# skmagiik_thing.net
KiCad netlist of a schematic drawn in EAGLE
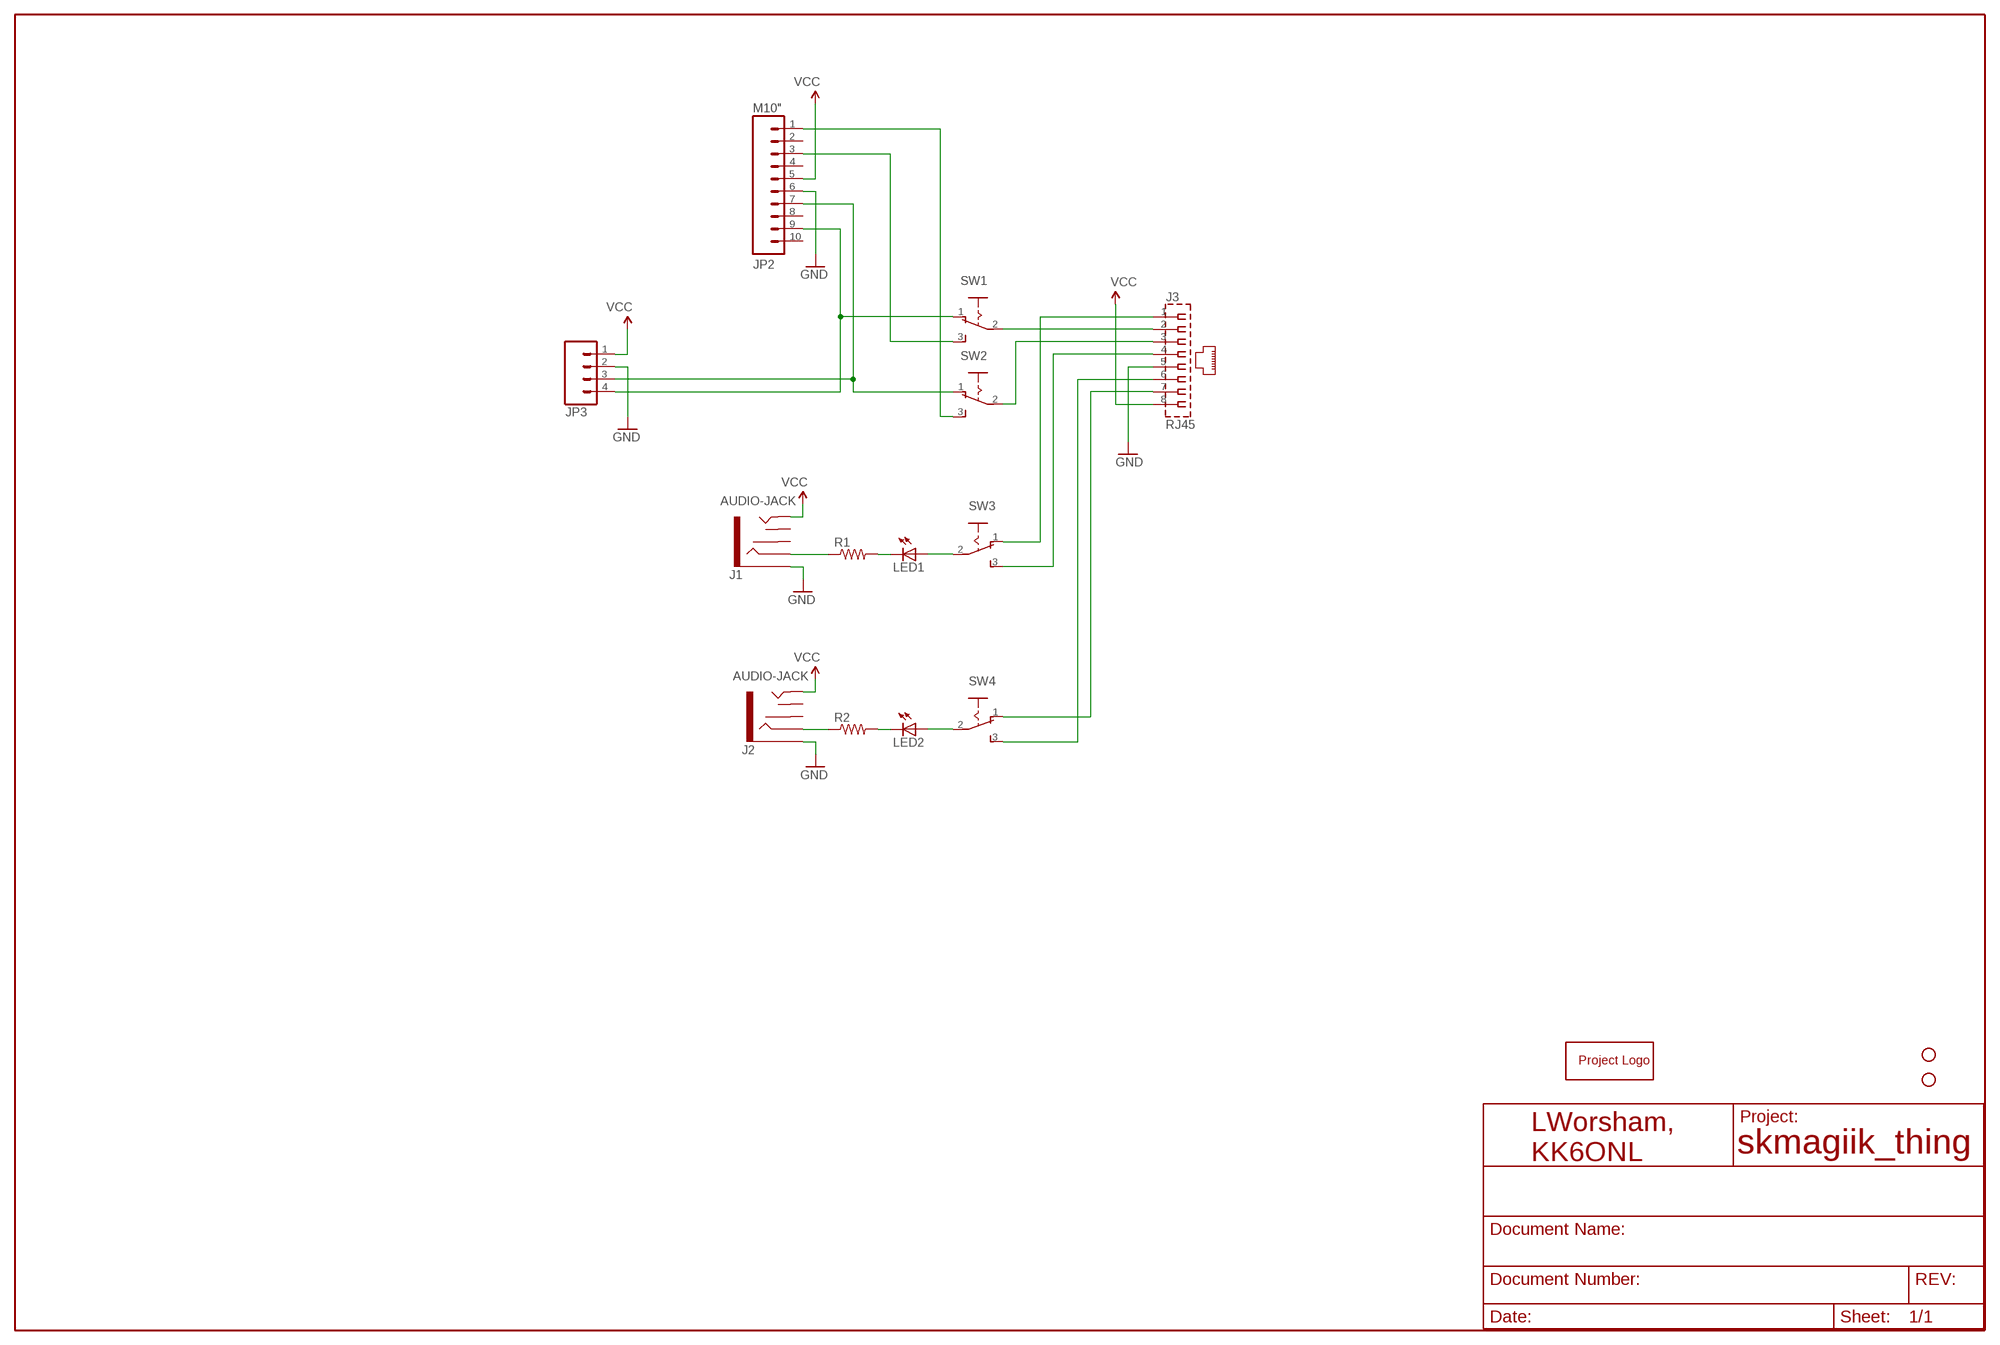
[diagram p0: schematic, sheet 1]

(export (version "E")
  (design (tool "Eeschema 10.0.6"))
  (components
    (comp (ref "J1")
      (value "AUDIO-JACK")
      (footprint "eagle-import:AUDIO-JACK")
      (libsource (lib "eagle-import") (part "AUDIO-JACK2PTH"))
    )
    (comp (ref "J2")
      (value "AUDIO-JACK")
      (footprint "eagle-import:AUDIO-JACK")
      (libsource (lib "eagle-import") (part "AUDIO-JACK2PTH"))
    )
    (comp (ref "J3")
      (value "RJ45")
      (footprint "eagle-import:RJ45")
      (libsource (lib "eagle-import") (part "RJ45"))
    )
    (comp (ref "JP2")
      (value "M10\"")
      (footprint "eagle-import:1X10")
      (fields (field (name "NO_PART") "1"))
      (libsource (lib "eagle-import") (part "M10{dblquote}"))
    )
    (comp (ref "JP3")
      (value "M04PTH")
      (footprint "eagle-import:1X04")
      (libsource (lib "eagle-import") (part "M04PTH"))
    )
    (comp (ref "LED1")
      (value "LED3MM")
      (footprint "eagle-import:LED3MM")
      (libsource (lib "eagle-import") (part "LED3MM"))
    )
    (comp (ref "LED2")
      (value "LED3MM")
      (footprint "eagle-import:LED3MM")
      (libsource (lib "eagle-import") (part "LED3MM"))
    )
    (comp (ref "R1")
      (value "R-US_0207/10")
      (footprint "eagle-import:0207_10")
      (libsource (lib "eagle-import") (part "R-US_0207/10"))
    )
    (comp (ref "R2")
      (value "R-US_0207/10")
      (footprint "eagle-import:0207_10")
      (libsource (lib "eagle-import") (part "R-US_0207/10"))
    )
    (comp (ref "STANDOFF3")
      (value "STAND-OFF")
      (footprint "eagle-import:STAND-OFF")
      (libsource (lib "eagle-import") (part "STAND-OFF"))
    )
    (comp (ref "STANDOFF5")
      (value "STAND-OFF")
      (footprint "eagle-import:STAND-OFF")
      (libsource (lib "eagle-import") (part "STAND-OFF"))
    )
    (comp (ref "SW1")
      (value "M251")
      (footprint "eagle-import:M251")
      (libsource (lib "eagle-import") (part "M251"))
    )
    (comp (ref "SW2")
      (value "M251")
      (footprint "eagle-import:M251")
      (libsource (lib "eagle-import") (part "M251"))
    )
    (comp (ref "SW3")
      (value "M251")
      (footprint "eagle-import:M251")
      (libsource (lib "eagle-import") (part "M251"))
    )
    (comp (ref "SW4")
      (value "M251")
      (footprint "eagle-import:M251")
      (libsource (lib "eagle-import") (part "M251"))
    )
    (comp (ref "U$2")
      (value "PROJECT_LOGO")
      (footprint "eagle-import:BMP_TEST")
      (libsource (lib "eagle-import") (part "PROJECT_LOGO"))
    )
  )
  (nets
    (net (code "1") (name "GND") (class "Default")
      (node (ref "J1") (pin "SLEEVE") (pinfunction "SLEEVE_SLEEVE") (pintype "bidirectional"))
      (node (ref "J2") (pin "SLEEVE") (pinfunction "SLEEVE_SLEEVE") (pintype "bidirectional"))
      (node (ref "J3") (pin "5") (pinfunction "5_5") (pintype "passive"))
      (node (ref "JP2") (pin "6") (pinfunction "6_6") (pintype "passive"))
      (node (ref "JP3") (pin "2") (pinfunction "2_2") (pintype "passive"))
    )
    (net (code "2") (name "Net-(J1-PadRING)") (class "Default")
      (node (ref "J1") (pin "RING") (pinfunction "RING_RING") (pintype "bidirectional"))
      (node (ref "R1") (pin "1") (pinfunction "1_1") (pintype "passive"))
    )
    (net (code "3") (name "Net-(J2-PadRING)") (class "Default")
      (node (ref "J2") (pin "RING") (pinfunction "RING_RING") (pintype "bidirectional"))
      (node (ref "R2") (pin "1") (pinfunction "1_1") (pintype "passive"))
    )
    (net (code "4") (name "Net-(LED1-C)") (class "Default")
      (node (ref "LED1") (pin "K") (pinfunction "C_K") (pintype "passive"))
      (node (ref "R1") (pin "2") (pinfunction "2_2") (pintype "passive"))
    )
    (net (code "5") (name "Net-(LED2-C)") (class "Default")
      (node (ref "LED2") (pin "K") (pinfunction "C_K") (pintype "passive"))
      (node (ref "R2") (pin "2") (pinfunction "2_2") (pintype "passive"))
    )
    (net (code "6") (name "Net-(SW1-O)") (class "Default")
      (node (ref "JP2") (pin "9") (pinfunction "9_9") (pintype "passive"))
      (node (ref "JP3") (pin "4") (pinfunction "4_4") (pintype "passive"))
      (node (ref "SW1") (pin "1") (pinfunction "O_1") (pintype "passive"))
    )
    (net (code "7") (name "Net-(SW1-P)") (class "Default")
      (node (ref "J3") (pin "2") (pinfunction "2_2") (pintype "passive"))
      (node (ref "SW1") (pin "2") (pinfunction "P_2") (pintype "passive"))
    )
    (net (code "8") (name "Net-(SW1-S)") (class "Default")
      (node (ref "JP2") (pin "3") (pinfunction "3_3") (pintype "passive"))
      (node (ref "SW1") (pin "3") (pinfunction "S_3") (pintype "passive"))
    )
    (net (code "9") (name "Net-(SW2-O)") (class "Default")
      (node (ref "JP2") (pin "7") (pinfunction "7_7") (pintype "passive"))
      (node (ref "JP3") (pin "3") (pinfunction "3_3") (pintype "passive"))
      (node (ref "SW2") (pin "1") (pinfunction "O_1") (pintype "passive"))
    )
    (net (code "10") (name "Net-(SW2-P)") (class "Default")
      (node (ref "J3") (pin "3") (pinfunction "3_3") (pintype "passive"))
      (node (ref "SW2") (pin "2") (pinfunction "P_2") (pintype "passive"))
    )
    (net (code "11") (name "Net-(SW2-S)") (class "Default")
      (node (ref "JP2") (pin "1") (pinfunction "1_1") (pintype "passive"))
      (node (ref "SW2") (pin "3") (pinfunction "S_3") (pintype "passive"))
    )
    (net (code "12") (name "Net-(SW3-O)") (class "Default")
      (node (ref "J3") (pin "1") (pinfunction "1_1") (pintype "passive"))
      (node (ref "SW3") (pin "1") (pinfunction "O_1") (pintype "passive"))
    )
    (net (code "13") (name "Net-(SW3-P)") (class "Default")
      (node (ref "LED1") (pin "A") (pinfunction "A_A") (pintype "passive"))
      (node (ref "SW3") (pin "2") (pinfunction "P_2") (pintype "passive"))
    )
    (net (code "14") (name "Net-(SW3-S)") (class "Default")
      (node (ref "J3") (pin "4") (pinfunction "4_4") (pintype "passive"))
      (node (ref "SW3") (pin "3") (pinfunction "S_3") (pintype "passive"))
    )
    (net (code "15") (name "Net-(SW4-O)") (class "Default")
      (node (ref "J3") (pin "7") (pinfunction "7_7") (pintype "passive"))
      (node (ref "SW4") (pin "1") (pinfunction "O_1") (pintype "passive"))
    )
    (net (code "16") (name "Net-(SW4-P)") (class "Default")
      (node (ref "LED2") (pin "A") (pinfunction "A_A") (pintype "passive"))
      (node (ref "SW4") (pin "2") (pinfunction "P_2") (pintype "passive"))
    )
    (net (code "17") (name "Net-(SW4-S)") (class "Default")
      (node (ref "J3") (pin "6") (pinfunction "6_6") (pintype "passive"))
      (node (ref "SW4") (pin "3") (pinfunction "S_3") (pintype "passive"))
    )
    (net (code "18") (name "VCC") (class "Default")
      (node (ref "J1") (pin "TIP") (pinfunction "TIP_TIP") (pintype "bidirectional"))
      (node (ref "J2") (pin "TIP") (pinfunction "TIP_TIP") (pintype "bidirectional"))
      (node (ref "J3") (pin "8") (pinfunction "8_8") (pintype "passive"))
      (node (ref "JP2") (pin "5") (pinfunction "5_5") (pintype "passive"))
      (node (ref "JP3") (pin "1") (pinfunction "1_1") (pintype "passive"))
    )
    (net (code "19") (name "unconnected-(J1-PadRSH)") (class "Default")
      (node (ref "J1") (pin "RSH") (pinfunction "RSH_RSH") (pintype "bidirectional"))
    )
    (net (code "20") (name "unconnected-(J1-PadTSH)") (class "Default")
      (node (ref "J1") (pin "TSH") (pinfunction "TSH_TSH") (pintype "bidirectional"))
    )
    (net (code "21") (name "unconnected-(J2-PadRSH)") (class "Default")
      (node (ref "J2") (pin "RSH") (pinfunction "RSH_RSH") (pintype "bidirectional"))
    )
    (net (code "22") (name "unconnected-(J2-PadTSH)") (class "Default")
      (node (ref "J2") (pin "TSH") (pinfunction "TSH_TSH") (pintype "bidirectional"))
    )
    (net (code "23") (name "unconnected-(JP2-Pad2)") (class "Default")
      (node (ref "JP2") (pin "2") (pinfunction "2_2") (pintype "passive"))
    )
    (net (code "24") (name "unconnected-(JP2-Pad4)") (class "Default")
      (node (ref "JP2") (pin "4") (pinfunction "4_4") (pintype "passive"))
    )
    (net (code "25") (name "unconnected-(JP2-Pad8)") (class "Default")
      (node (ref "JP2") (pin "8") (pinfunction "8_8") (pintype "passive"))
    )
    (net (code "26") (name "unconnected-(JP2-Pad10)") (class "Default")
      (node (ref "JP2") (pin "10") (pinfunction "10_10") (pintype "passive"))
    )
  )
)
